# 3V3_SYS_SUPPLY.net
KiCad netlist of a schematic drawn in Altium Designer
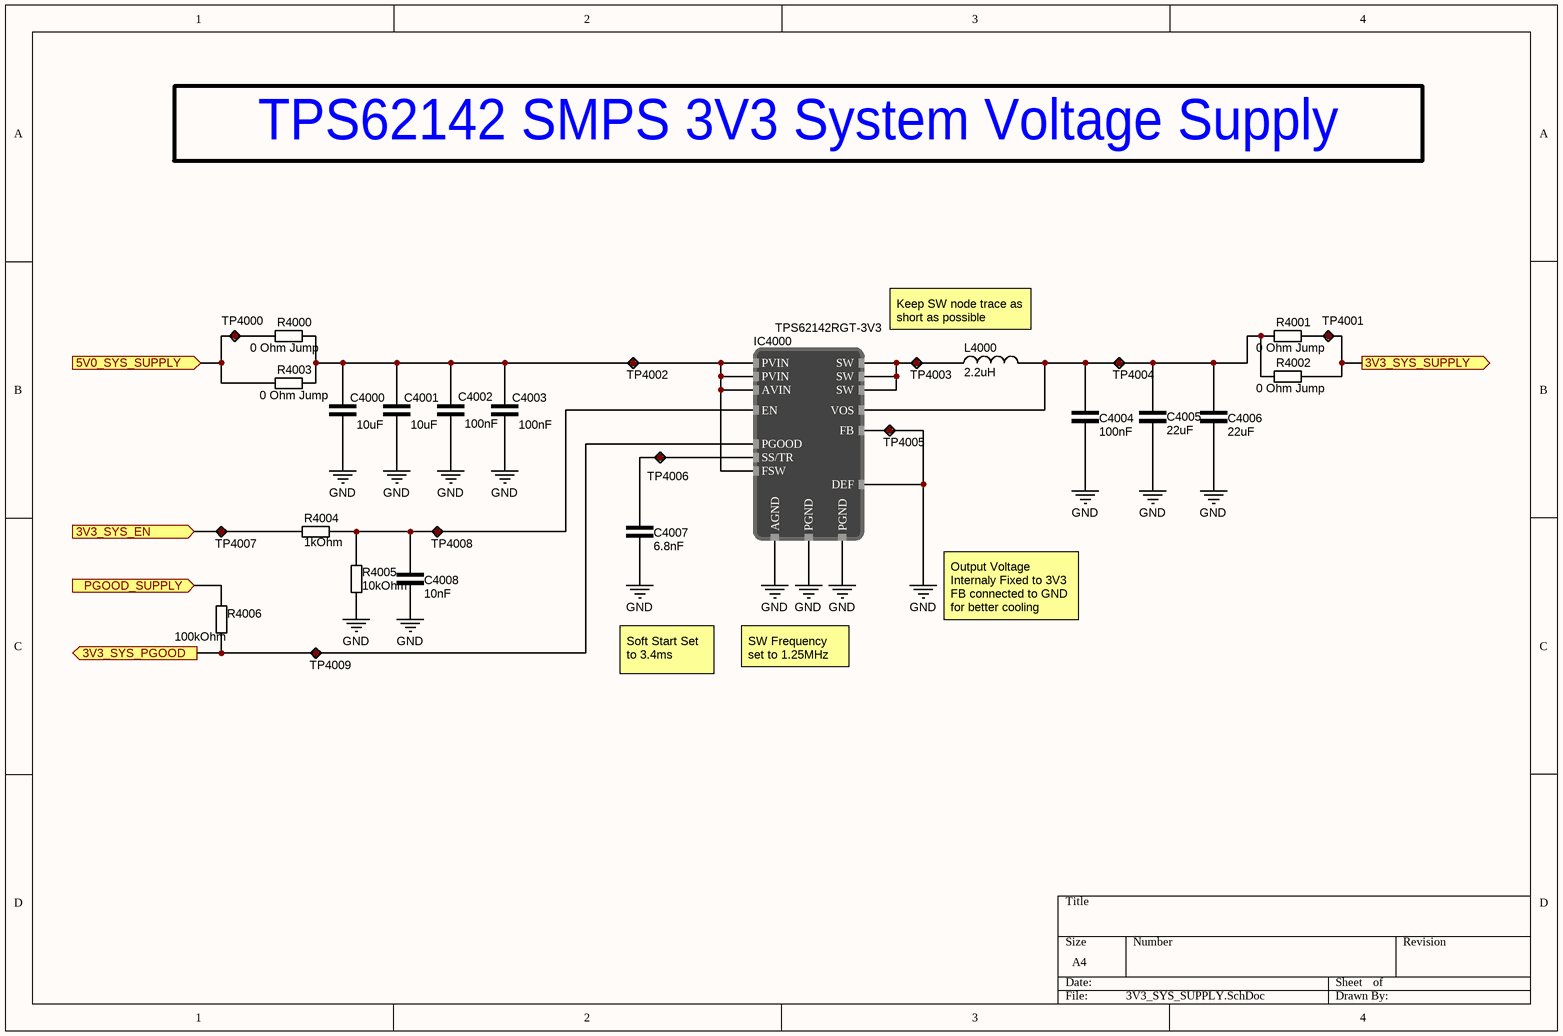
[diagram p0: 3V3_SYS_SUPPLY.SchDoc]

(export (version "E")
  (design (tool "Eeschema 10.0.6"))
  (components
    (comp (ref "C4000")
      (value "10uF")
      (footprint "CAP_0805")
      (description "10 µF ±10% 25V Ceramic Capacitor X5R 0805 (2012 Metric)")
      (fields (field (name "DIGIKEY PART NUMBER") "445-5984-1-ND"))
      (libsource (lib "CapacitorsIntegrated") (part "C000002"))
    )
    (comp (ref "C4001")
      (value "10uF")
      (footprint "CAP_0805")
      (description "10 µF ±10% 25V Ceramic Capacitor X5R 0805 (2012 Metric)")
      (fields (field (name "DIGIKEY PART NUMBER") "445-5984-1-ND"))
      (libsource (lib "CapacitorsIntegrated") (part "C000002"))
    )
    (comp (ref "C4002")
      (value "100nF")
      (footprint "CAP_0603")
      (description "0.1 µF ±10% 25V Ceramic Capacitor X7R 0603 (1608 Metric)")
      (fields (field (name "DIGIKEY PART NUMBER") "478-KAM15AR71E104KTCT-ND"))
      (libsource (lib "") (part "C000007_1"))
    )
    (comp (ref "C4003")
      (value "100nF")
      (footprint "CAP_0603")
      (description "0.1 µF ±10% 25V Ceramic Capacitor X7R 0603 (1608 Metric)")
      (fields (field (name "DIGIKEY PART NUMBER") "478-KAM15AR71E104KTCT-ND"))
      (libsource (lib "CapacitorsIntegrated") (part "C000007"))
    )
    (comp (ref "C4004")
      (value "100nF")
      (footprint "CAP_0603")
      (description "0.1 µF ±10% 25V Ceramic Capacitor X7R 0603 (1608 Metric)")
      (fields (field (name "DIGIKEY PART NUMBER") "478-KAM15AR71E104KTCT-ND"))
      (libsource (lib "CapacitorsIntegrated") (part "C000007"))
    )
    (comp (ref "C4005")
      (value "22uF")
      (footprint "CAP_0805")
      (description "22 µF ±20% 25V Ceramic Capacitor X5R 0805 (2012 Metric)")
      (fields (field (name "DIGIKEY PART NUMBER") "445-9112-1-ND"))
      (libsource (lib "") (part "C000001_1"))
    )
    (comp (ref "C4006")
      (value "22uF")
      (footprint "CAP_0805")
      (description "22 µF ±20% 25V Ceramic Capacitor X5R 0805 (2012 Metric)")
      (fields (field (name "DIGIKEY PART NUMBER") "445-9112-1-ND"))
      (libsource (lib "CapacitorsIntegrated") (part "C000001"))
    )
    (comp (ref "C4007")
      (value "6.8nF")
      (footprint "CAP_0603")
      (description "6800 pF ±10% 25V Ceramic Capacitor X7R 0603 (1608 Metric)")
      (fields (field (name "DIGIKEY PART NUMBER") "311-4090-1-ND"))
      (libsource (lib "CapacitorsIntegrated") (part "C000023"))
    )
    (comp (ref "C4008")
      (value "10nF")
      (footprint "CAP_0603")
      (description "10000 pF ±20% 25V Ceramic Capacitor X7R 0603 (1608 Metric)")
      (fields (field (name "DIGIKEY PART NUMBER") "478-KGM15AR71E103MTCT-ND"))
      (libsource (lib "CapacitorsIntegrated") (part "C000005"))
    )
    (comp (ref "IC4000")
      (value "TPS62142RGT-3V3")
      (footprint "QFN50P300X300X100_HS-17N")
      (description "Buck Switching Regulator IC Positive Fixed 3.3V 1 Output 2A 16-VFQFN Exposed Pad")
      (fields
        (field (name "DIGIKEY PART NUMBER") "296-29940-1-ND")
        (field (name "MOUSER PART NUMBER") "595-TPS62142RGTT")
      )
      (libsource (lib "IntegratedCircuits") (part "TPS62142RGT"))
    )
    (comp (ref "L4000")
      (value "2.2uH")
      (footprint "INDM4441X20N")
      (description "FIXED IND 2.2UH 4A 61 MOHM SMD")
      (fields (field (name "DIGIKEY PART NUMBER") "SRP4020TA-2R2MCT-ND"))
      (libsource (lib "InductorIntegrated") (part "L000008"))
    )
    (comp (ref "R4000")
      (value "0 Ohm Jump")
      (footprint "RES_0805")
      (description "0 Ohms Jumper Chip Resistor 0805 (2012 Metric) Automotive AEC-Q200 Thick Film")
      (fields (field (name "DIGIKEY PART NUMBER") "P0.0ACT-ND"))
      (libsource (lib "ResistorsIntegrated") (part "R000011"))
    )
    (comp (ref "R4001")
      (value "0 Ohm Jump")
      (footprint "RES_0805")
      (description "0 Ohms Jumper Chip Resistor 0805 (2012 Metric) Automotive AEC-Q200 Thick Film")
      (fields (field (name "DIGIKEY PART NUMBER") "P0.0ACT-ND"))
      (libsource (lib "ResistorsIntegrated") (part "R000011"))
    )
    (comp (ref "R4002")
      (value "0 Ohm Jump")
      (footprint "RES_0805")
      (description "0 Ohms Jumper Chip Resistor 0805 (2012 Metric) Automotive AEC-Q200 Thick Film")
      (fields (field (name "DIGIKEY PART NUMBER") "P0.0ACT-ND"))
      (libsource (lib "ResistorsIntegrated") (part "R000011"))
    )
    (comp (ref "R4003")
      (value "0 Ohm Jump")
      (footprint "RES_0805")
      (description "0 Ohms Jumper Chip Resistor 0805 (2012 Metric) Automotive AEC-Q200 Thick Film")
      (fields (field (name "DIGIKEY PART NUMBER") "P0.0ACT-ND"))
      (libsource (lib "ResistorsIntegrated") (part "R000011"))
    )
    (comp (ref "R4004")
      (value "1kOhm")
      (footprint "RES_0603")
      (description "1 kOhms ±1% 0.125W, 1/8W Chip Resistor 0603 (1608 Metric) Anti-Sulfur Thin Film")
      (fields (field (name "DIGIKEY PART NUMBER") "MCT0603-1.00K-CFCT-ND"))
      (libsource (lib "ResistorsIntegrated") (part "R000004"))
    )
    (comp (ref "R4005")
      (value "10kOhm")
      (footprint "RES_0603")
      (description "10 kOhms ±1% 0.125W, 1/8W Chip Resistor 0603 (1608 Metric) Anti-Sulfur Thin Film")
      (fields (field (name "DIGIKEY PART NUMBER") "MCT0603-10.0K-CFCT-ND"))
      (libsource (lib "ResistorsIntegrated") (part "R000001"))
    )
    (comp (ref "R4006")
      (value "100kOhm")
      (footprint "RES_0603")
      (description "100 kOhms ±1% 0.1W, 1/10W Chip Resistor 0603 (1608 Metric) Automotive AEC-Q200 Thick Film")
      (fields (field (name "DIGIKEY PART NUMBER") "RMCF0603FG100KCT-ND"))
      (libsource (lib "ResistorsIntegrated") (part "R000006"))
    )
    (comp (ref "TP4000")
      (value "Test point")
      (footprint "TestPoint")
      (description "Test point 1mm")
      (libsource (lib "IntegratedCircuits") (part "TP002"))
    )
    (comp (ref "TP4001")
      (value "Test point")
      (footprint "TestPoint")
      (description "Test point 1mm")
      (libsource (lib "IntegratedCircuits") (part "TP002"))
    )
    (comp (ref "TP4002")
      (value "Test point")
      (footprint "TestPoint")
      (description "Test point 1mm")
      (libsource (lib "IntegratedCircuits") (part "TP002"))
    )
    (comp (ref "TP4003")
      (value "Test point")
      (footprint "TestPoint")
      (description "Test point 1mm")
      (libsource (lib "IntegratedCircuits") (part "TP002"))
    )
    (comp (ref "TP4004")
      (value "Test point")
      (footprint "TestPoint")
      (description "Test point 1mm")
      (libsource (lib "IntegratedCircuits") (part "TP002"))
    )
    (comp (ref "TP4005")
      (value "Test point")
      (footprint "TestPoint")
      (description "Test point 1mm")
      (libsource (lib "IntegratedCircuits") (part "TP002"))
    )
    (comp (ref "TP4006")
      (value "Test point")
      (footprint "TestPoint")
      (description "Test point 1mm")
      (libsource (lib "IntegratedCircuits") (part "TP002"))
    )
    (comp (ref "TP4007")
      (value "Test point")
      (footprint "TestPoint")
      (description "Test point 1mm")
      (libsource (lib "IntegratedCircuits") (part "TP002"))
    )
    (comp (ref "TP4008")
      (value "Test point")
      (footprint "TestPoint")
      (description "Test point 1mm")
      (libsource (lib "IntegratedCircuits") (part "TP002"))
    )
    (comp (ref "TP4009")
      (value "Test point")
      (footprint "TestPoint")
      (description "Test point 1mm")
      (libsource (lib "IntegratedCircuits") (part "TP002"))
    )
  )
  (nets
    (net (code "1") (name "/3V3_SYS_EN") (class "Default")
      (node (ref "R4004") (pin "1") (pinfunction "1_1") (pintype "passive"))
      (node (ref "TP4007") (pin "1") (pinfunction "1_1") (pintype "passive"))
    )
    (net (code "2") (name "/3V3_SYS_PGOOD") (class "Default")
      (node (ref "IC4000") (pin "4") (pinfunction "PGOOD_4") (pintype "passive"))
      (node (ref "R4006") (pin "1") (pinfunction "1_1") (pintype "passive"))
      (node (ref "TP4009") (pin "1") (pinfunction "1_1") (pintype "passive"))
    )
    (net (code "3") (name "/3V3_SYS_SUPPLY") (class "Default")
      (node (ref "R4001") (pin "2") (pinfunction "2_2") (pintype "passive"))
      (node (ref "R4002") (pin "2") (pinfunction "2_2") (pintype "passive"))
      (node (ref "TP4001") (pin "1") (pinfunction "1_1") (pintype "passive"))
    )
    (net (code "4") (name "/5V0_SYS_SUPPLY") (class "Default")
      (node (ref "R4000") (pin "1") (pinfunction "1_1") (pintype "passive"))
      (node (ref "R4003") (pin "1") (pinfunction "1_1") (pintype "passive"))
      (node (ref "TP4000") (pin "1") (pinfunction "1_1") (pintype "passive"))
    )
    (net (code "5") (name "/PGOOD_SUPPLY") (class "Default")
      (node (ref "R4006") (pin "2") (pinfunction "2_2") (pintype "passive"))
    )
    (net (code "6") (name "GND") (class "Default")
      (node (ref "C4000") (pin "1") (pinfunction "1_1") (pintype "passive"))
      (node (ref "C4001") (pin "1") (pinfunction "1_1") (pintype "passive"))
      (node (ref "C4002") (pin "2") (pinfunction "2_2") (pintype "passive"))
      (node (ref "C4003") (pin "1") (pinfunction "1_1") (pintype "passive"))
      (node (ref "C4004") (pin "1") (pinfunction "1_1") (pintype "passive"))
      (node (ref "C4005") (pin "1") (pinfunction "1_1") (pintype "passive"))
      (node (ref "C4006") (pin "2") (pinfunction "2_2") (pintype "passive"))
      (node (ref "C4007") (pin "1") (pinfunction "1_1") (pintype "passive"))
      (node (ref "C4008") (pin "1") (pinfunction "1_1") (pintype "passive"))
      (node (ref "IC4000") (pin "15") (pinfunction "PGND_15") (pintype "passive"))
      (node (ref "IC4000") (pin "16") (pinfunction "PGND_16") (pintype "passive"))
      (node (ref "IC4000") (pin "5") (pinfunction "FB_5") (pintype "passive"))
      (node (ref "IC4000") (pin "6") (pinfunction "AGND_6") (pintype "passive"))
      (node (ref "IC4000") (pin "8") (pinfunction "DEF_8") (pintype "passive"))
      (node (ref "R4005") (pin "1") (pinfunction "1_1") (pintype "passive"))
      (node (ref "TP4005") (pin "1") (pinfunction "1_1") (pintype "passive"))
    )
    (net (code "7") (name "Net-(IC4000-AVIN)") (class "Default")
      (node (ref "C4000") (pin "2") (pinfunction "2_2") (pintype "passive"))
      (node (ref "C4001") (pin "2") (pinfunction "2_2") (pintype "passive"))
      (node (ref "C4002") (pin "1") (pinfunction "1_1") (pintype "passive"))
      (node (ref "C4003") (pin "2") (pinfunction "2_2") (pintype "passive"))
      (node (ref "IC4000") (pin "10") (pinfunction "AVIN_10") (pintype "passive"))
      (node (ref "IC4000") (pin "11") (pinfunction "PVIN_11") (pintype "passive"))
      (node (ref "IC4000") (pin "12") (pinfunction "PVIN_12") (pintype "passive"))
      (node (ref "IC4000") (pin "7") (pinfunction "FSW_7") (pintype "passive"))
      (node (ref "R4000") (pin "2") (pinfunction "2_2") (pintype "passive"))
      (node (ref "R4003") (pin "2") (pinfunction "2_2") (pintype "passive"))
      (node (ref "TP4002") (pin "1") (pinfunction "1_1") (pintype "passive"))
    )
    (net (code "8") (name "Net-(IC4000-EN)") (class "Default")
      (node (ref "C4008") (pin "2") (pinfunction "2_2") (pintype "passive"))
      (node (ref "IC4000") (pin "13") (pinfunction "EN_13") (pintype "passive"))
      (node (ref "R4004") (pin "2") (pinfunction "2_2") (pintype "passive"))
      (node (ref "R4005") (pin "2") (pinfunction "2_2") (pintype "passive"))
      (node (ref "TP4008") (pin "1") (pinfunction "1_1") (pintype "passive"))
    )
    (net (code "9") (name "Net-(IC4000-SS{slash}TR)") (class "Default")
      (node (ref "C4007") (pin "2") (pinfunction "2_2") (pintype "passive"))
      (node (ref "IC4000") (pin "9") (pinfunction "SS/TR_9") (pintype "passive"))
      (node (ref "TP4006") (pin "1") (pinfunction "1_1") (pintype "passive"))
    )
    (net (code "10") (name "Net-(IC4000-SW-Pad1)") (class "Default")
      (node (ref "IC4000") (pin "1") (pinfunction "SW_1") (pintype "passive"))
      (node (ref "IC4000") (pin "2") (pinfunction "SW_2") (pintype "passive"))
      (node (ref "IC4000") (pin "3") (pinfunction "SW_3") (pintype "passive"))
      (node (ref "L4000") (pin "1") (pinfunction "1_1") (pintype "passive"))
      (node (ref "TP4003") (pin "1") (pinfunction "1_1") (pintype "passive"))
    )
    (net (code "11") (name "Net-(IC4000-VOS)") (class "Default")
      (node (ref "C4004") (pin "2") (pinfunction "2_2") (pintype "passive"))
      (node (ref "C4005") (pin "2") (pinfunction "2_2") (pintype "passive"))
      (node (ref "C4006") (pin "1") (pinfunction "1_1") (pintype "passive"))
      (node (ref "IC4000") (pin "14") (pinfunction "VOS_14") (pintype "passive"))
      (node (ref "L4000") (pin "2") (pinfunction "2_2") (pintype "passive"))
      (node (ref "R4001") (pin "1") (pinfunction "1_1") (pintype "passive"))
      (node (ref "R4002") (pin "1") (pinfunction "1_1") (pintype "passive"))
      (node (ref "TP4004") (pin "1") (pinfunction "1_1") (pintype "passive"))
    )
  )
)
